# Gigabit_Ethernet.net
KiCad netlist of a schematic drawn in Altium Designer
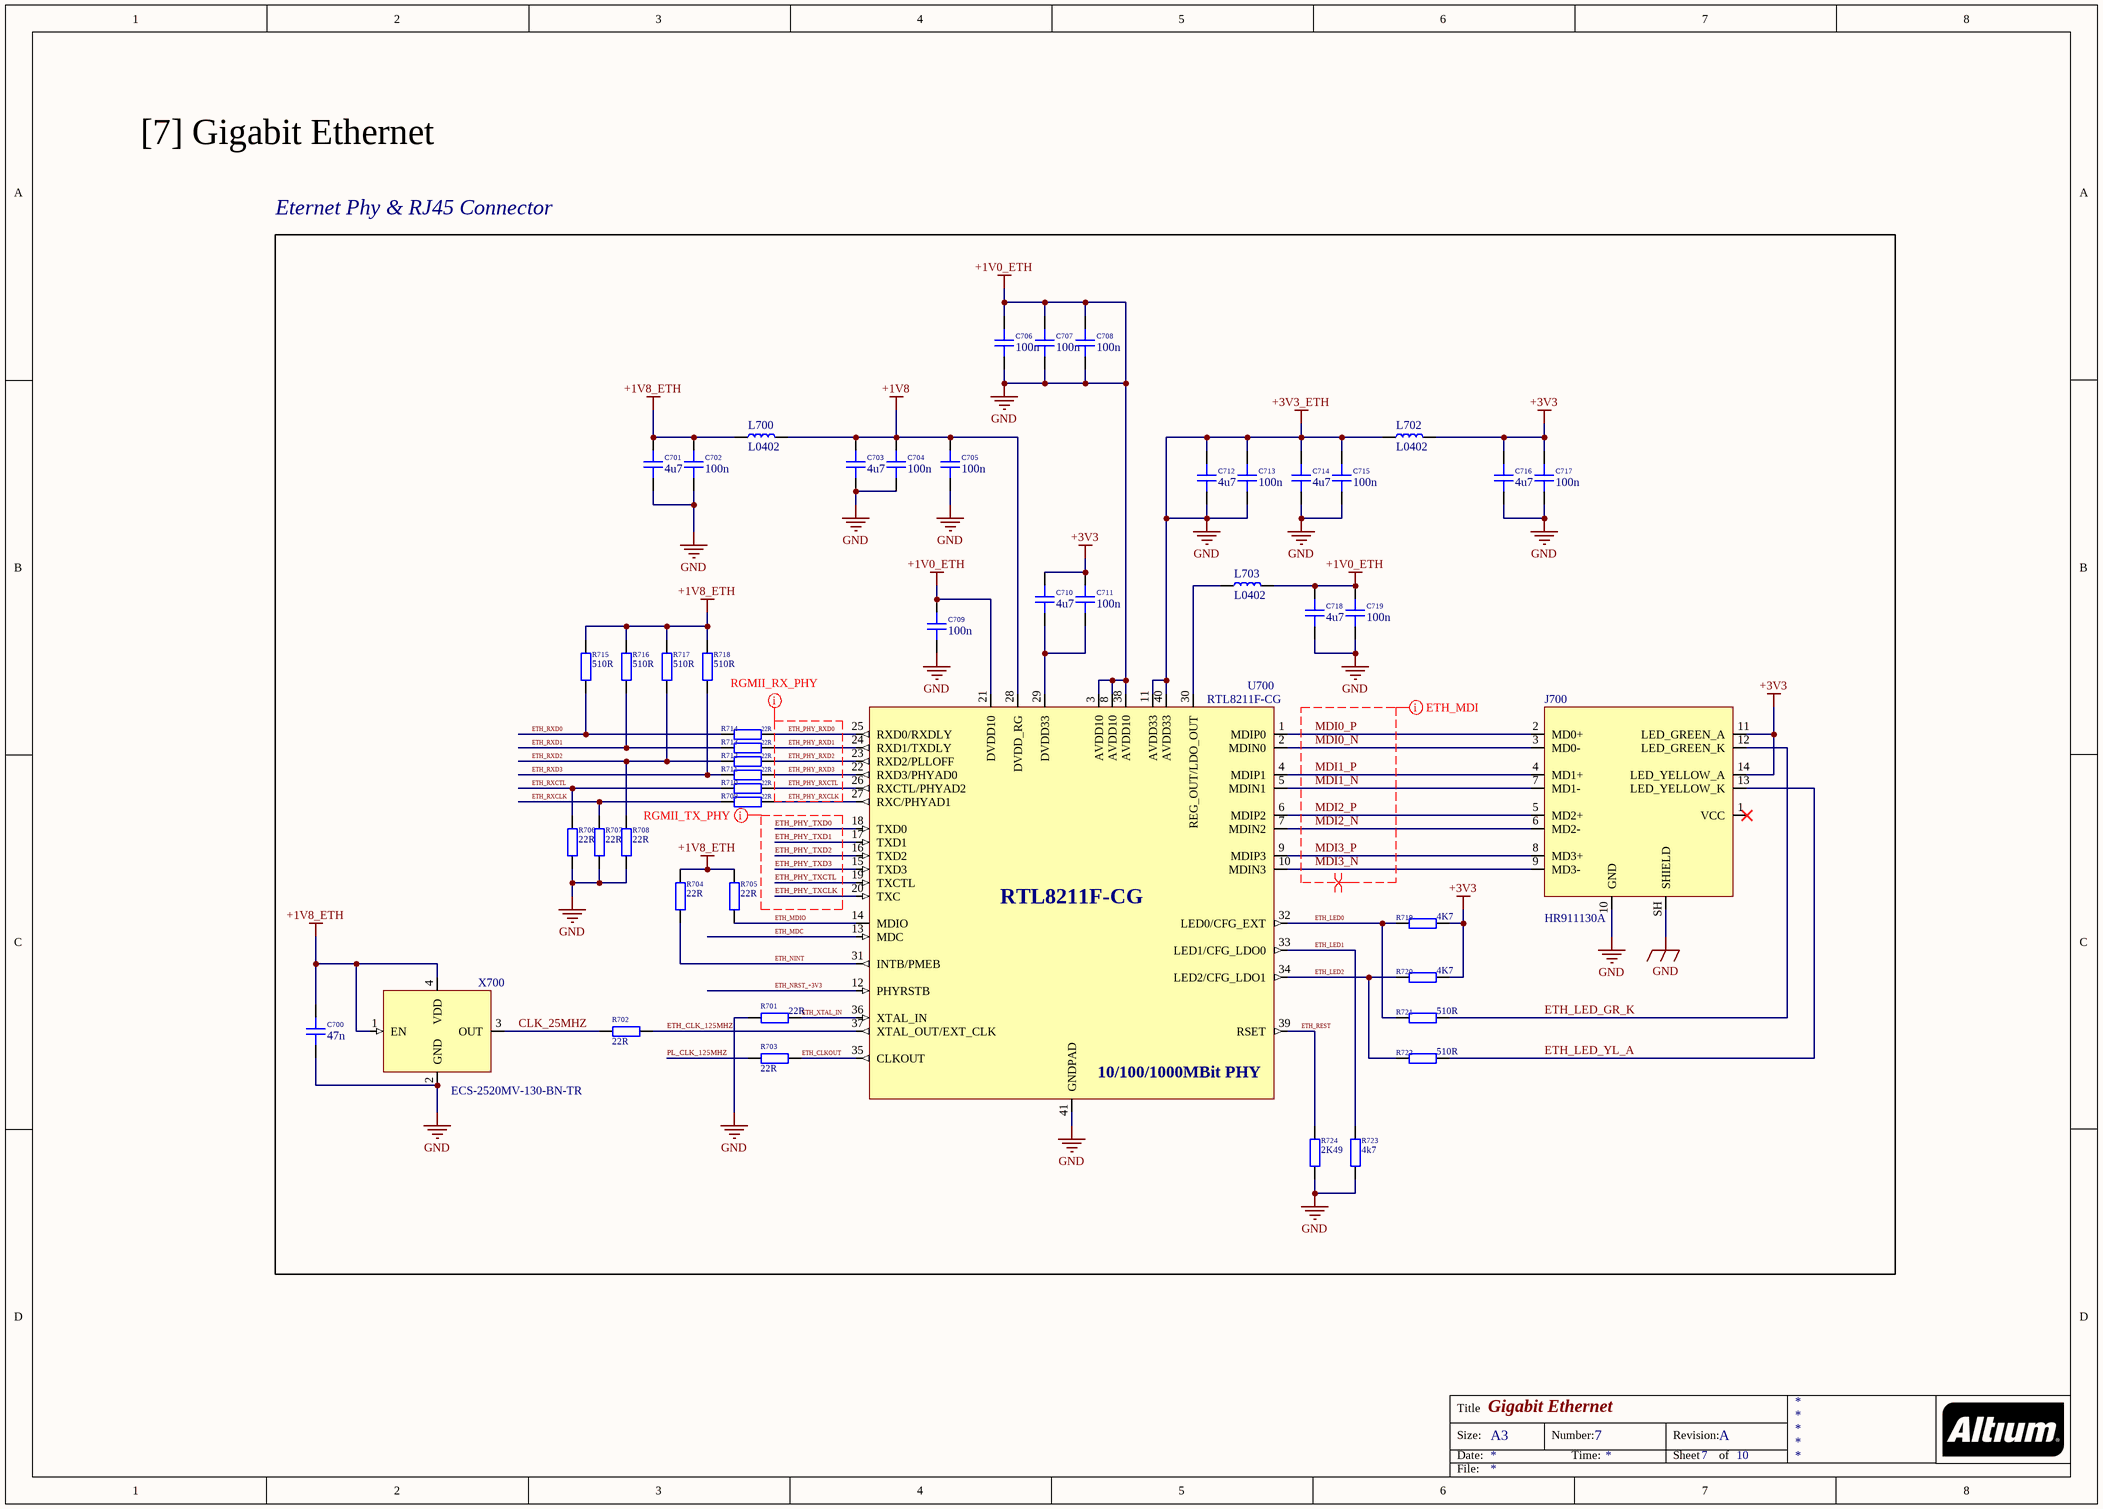
[diagram p0: Gigabit Ethernet.SchDoc]

(export (version "E")
  (design (tool "Eeschema 10.0.6"))
  (components
    (comp (ref "C700")
      (value "47n")
      (footprint "CAP_1210")
      (description "Capacitor SMD 1210")
      (libsource (lib "Schematic-Lib-PhilsLab") (part "CAP_1210"))
    )
    (comp (ref "C701")
      (value "4u7")
      (footprint "CAP_1210")
      (description "Capacitor SMD 1210")
      (libsource (lib "Schematic-Lib-PhilsLab") (part "CAP_1210"))
    )
    (comp (ref "C702")
      (value "100n")
      (footprint "CAP_1210")
      (description "Capacitor SMD 1210")
      (libsource (lib "Schematic-Lib-PhilsLab") (part "CAP_1210"))
    )
    (comp (ref "C703")
      (value "4u7")
      (footprint "CAP_1210")
      (description "Capacitor SMD 1210")
      (libsource (lib "Schematic-Lib-PhilsLab") (part "CAP_1210"))
    )
    (comp (ref "C704")
      (value "100n")
      (footprint "CAP_1210")
      (description "Capacitor SMD 1210")
      (libsource (lib "Schematic-Lib-PhilsLab") (part "CAP_1210"))
    )
    (comp (ref "C705")
      (value "100n")
      (footprint "CAP_1210")
      (description "Capacitor SMD 1210")
      (libsource (lib "Schematic-Lib-PhilsLab") (part "CAP_1210"))
    )
    (comp (ref "C706")
      (value "100n")
      (footprint "CAP_1210")
      (description "Capacitor SMD 1210")
      (libsource (lib "Schematic-Lib-PhilsLab") (part "CAP_1210"))
    )
    (comp (ref "C707")
      (value "100n")
      (footprint "CAP_1210")
      (description "Capacitor SMD 1210")
      (libsource (lib "Schematic-Lib-PhilsLab") (part "CAP_1210"))
    )
    (comp (ref "C708")
      (value "100n")
      (footprint "CAP_1210")
      (description "Capacitor SMD 1210")
      (libsource (lib "Schematic-Lib-PhilsLab") (part "CAP_1210"))
    )
    (comp (ref "C709")
      (value "100n")
      (footprint "CAP_1210")
      (description "Capacitor SMD 1210")
      (libsource (lib "Schematic-Lib-PhilsLab") (part "CAP_1210"))
    )
    (comp (ref "C710")
      (value "4u7")
      (footprint "CAP_1210")
      (description "Capacitor SMD 1210")
      (libsource (lib "Schematic-Lib-PhilsLab") (part "CAP_1210"))
    )
    (comp (ref "C711")
      (value "100n")
      (footprint "CAP_1210")
      (description "Capacitor SMD 1210")
      (libsource (lib "Schematic-Lib-PhilsLab") (part "CAP_1210"))
    )
    (comp (ref "C712")
      (value "4u7")
      (footprint "CAP_1210")
      (description "Capacitor SMD 1210")
      (libsource (lib "Schematic-Lib-PhilsLab") (part "CAP_1210"))
    )
    (comp (ref "C713")
      (value "100n")
      (footprint "CAP_1210")
      (description "Capacitor SMD 1210")
      (libsource (lib "Schematic-Lib-PhilsLab") (part "CAP_1210"))
    )
    (comp (ref "C714")
      (value "4u7")
      (footprint "CAP_1210")
      (description "Capacitor SMD 1210")
      (libsource (lib "Schematic-Lib-PhilsLab") (part "CAP_1210"))
    )
    (comp (ref "C715")
      (value "100n")
      (footprint "CAP_1210")
      (description "Capacitor SMD 1210")
      (libsource (lib "Schematic-Lib-PhilsLab") (part "CAP_1210"))
    )
    (comp (ref "C716")
      (value "4u7")
      (footprint "CAP_1210")
      (description "Capacitor SMD 1210")
      (libsource (lib "Schematic-Lib-PhilsLab") (part "CAP_1210"))
    )
    (comp (ref "C717")
      (value "100n")
      (footprint "CAP_1210")
      (description "Capacitor SMD 1210")
      (libsource (lib "Schematic-Lib-PhilsLab") (part "CAP_1210"))
    )
    (comp (ref "C718")
      (value "4u7")
      (footprint "CAP_1210")
      (description "Capacitor SMD 1210")
      (libsource (lib "Schematic-Lib-PhilsLab") (part "CAP_1210"))
    )
    (comp (ref "C719")
      (value "100n")
      (footprint "CAP_1210")
      (description "Capacitor SMD 1210")
      (libsource (lib "Schematic-Lib-PhilsLab") (part "CAP_1210"))
    )
    (comp (ref "J700")
      (value "HR911130A")
      (footprint "HR911130A")
      (description "100/1000Base-T Magnetics Single-Port RJ45 Connector with Integrated Magnetics and LEDs")
      (fields (field (name "MANUFACTURER") "Hanrun"))
      (libsource (lib "Schematic-Lib-PhilsLab") (part "HR911130A"))
    )
    (comp (ref "L700")
      (value "L0402")
      (footprint "IND_0402")
      (description "Inductor SMD 0402")
      (libsource (lib "Schematic-Lib-PhilsLab") (part "IND_0402"))
    )
    (comp (ref "L702")
      (value "L0402")
      (footprint "IND_0402")
      (description "Inductor SMD 0402")
      (libsource (lib "Schematic-Lib-PhilsLab") (part "IND_0402"))
    )
    (comp (ref "L703")
      (value "L0402")
      (footprint "IND_0402")
      (description "Inductor SMD 0402")
      (libsource (lib "Schematic-Lib-PhilsLab") (part "IND_0402"))
    )
    (comp (ref "R701")
      (value "22R")
      (footprint "RES_0402")
      (description "Resistor SMD 0402")
      (libsource (lib "Schematic-Lib-PhilsLab") (part "RES_0402"))
    )
    (comp (ref "R702")
      (value "22R")
      (footprint "RES_0402")
      (description "Resistor SMD 0402")
      (libsource (lib "Schematic-Lib-PhilsLab") (part "RES_0402"))
    )
    (comp (ref "R703")
      (value "22R")
      (footprint "RES_0402")
      (description "Resistor SMD 0402")
      (libsource (lib "Schematic-Lib-PhilsLab") (part "RES_0402"))
    )
    (comp (ref "R704")
      (value "22R")
      (footprint "RES_0402")
      (description "Resistor SMD 0402")
      (libsource (lib "Schematic-Lib-PhilsLab") (part "RES_0402"))
    )
    (comp (ref "R705")
      (value "22R")
      (footprint "RES_0402")
      (description "Resistor SMD 0402")
      (libsource (lib "Schematic-Lib-PhilsLab") (part "RES_0402"))
    )
    (comp (ref "R706")
      (value "22R")
      (footprint "RES_0402")
      (description "Resistor SMD 0402")
      (libsource (lib "Schematic-Lib-PhilsLab") (part "RES_0402"))
    )
    (comp (ref "R707")
      (value "22R")
      (footprint "RES_0402")
      (description "Resistor SMD 0402")
      (libsource (lib "Schematic-Lib-PhilsLab") (part "RES_0402"))
    )
    (comp (ref "R708")
      (value "22R")
      (footprint "RES_0402")
      (description "Resistor SMD 0402")
      (libsource (lib "Schematic-Lib-PhilsLab") (part "RES_0402"))
    )
    (comp (ref "R709")
      (value "22R")
      (footprint "RES_0402")
      (description "Resistor SMD 0402")
      (libsource (lib "Schematic-Lib-PhilsLab") (part "RES_0402"))
    )
    (comp (ref "R710")
      (value "22R")
      (footprint "RES_0402")
      (description "Resistor SMD 0402")
      (libsource (lib "Schematic-Lib-PhilsLab") (part "RES_0402"))
    )
    (comp (ref "R711")
      (value "22R")
      (footprint "RES_0402")
      (description "Resistor SMD 0402")
      (libsource (lib "Schematic-Lib-PhilsLab") (part "RES_0402"))
    )
    (comp (ref "R712")
      (value "22R")
      (footprint "RES_0402")
      (description "Resistor SMD 0402")
      (libsource (lib "Schematic-Lib-PhilsLab") (part "RES_0402"))
    )
    (comp (ref "R713")
      (value "22R")
      (footprint "RES_0402")
      (description "Resistor SMD 0402")
      (libsource (lib "Schematic-Lib-PhilsLab") (part "RES_0402"))
    )
    (comp (ref "R714")
      (value "22R")
      (footprint "RES_0402")
      (description "Resistor SMD 0402")
      (libsource (lib "Schematic-Lib-PhilsLab") (part "RES_0402"))
    )
    (comp (ref "R715")
      (value "510R")
      (footprint "RES_0402")
      (description "Resistor SMD 0402")
      (libsource (lib "Schematic-Lib-PhilsLab") (part "RES_0402"))
    )
    (comp (ref "R716")
      (value "510R")
      (footprint "RES_0402")
      (description "Resistor SMD 0402")
      (libsource (lib "Schematic-Lib-PhilsLab") (part "RES_0402"))
    )
    (comp (ref "R717")
      (value "510R")
      (footprint "RES_0402")
      (description "Resistor SMD 0402")
      (libsource (lib "Schematic-Lib-PhilsLab") (part "RES_0402"))
    )
    (comp (ref "R718")
      (value "510R")
      (footprint "RES_0402")
      (description "Resistor SMD 0402")
      (libsource (lib "Schematic-Lib-PhilsLab") (part "RES_0402"))
    )
    (comp (ref "R719")
      (value "4K7")
      (footprint "RES_0402")
      (description "Resistor SMD 0402")
      (libsource (lib "Schematic-Lib-PhilsLab") (part "RES_0402"))
    )
    (comp (ref "R720")
      (value "4K7")
      (footprint "RES_0402")
      (description "Resistor SMD 0402")
      (libsource (lib "Schematic-Lib-PhilsLab") (part "RES_0402"))
    )
    (comp (ref "R721")
      (value "510R")
      (footprint "RES_0402")
      (description "Resistor SMD 0402")
      (libsource (lib "Schematic-Lib-PhilsLab") (part "RES_0402"))
    )
    (comp (ref "R722")
      (value "510R")
      (footprint "RES_0402")
      (description "Resistor SMD 0402")
      (libsource (lib "Schematic-Lib-PhilsLab") (part "RES_0402"))
    )
    (comp (ref "R723")
      (value "4k7")
      (footprint "RES_0402")
      (description "Resistor SMD 0402")
      (libsource (lib "Schematic-Lib-PhilsLab") (part "RES_0402"))
    )
    (comp (ref "R724")
      (value "2K49")
      (footprint "RES_0402")
      (description "Resistor SMD 0402")
      (libsource (lib "Schematic-Lib-PhilsLab") (part "RES_0402"))
    )
    (comp (ref "U700")
      (value "RTL8211F-CG")
      (footprint "QFN-40-0.4-EP")
      (description "INTEGRATED 10/100/1000M ETHERNET PRECISION TRANSCEIVER")
      (fields (field (name "MANUFACTURER") "Realtek"))
      (libsource (lib "Schematic-Lib-PhilsLab") (part "RTL8211F-CG"))
    )
    (comp (ref "X700")
      (value "ECS-2520MV-130-BN-TR")
      (footprint "XTAL_2520")
      (fields (field (name "MANUFACTURER") "ECS"))
      (libsource (lib "Schematic-Lib-PhilsLab") (part "ECS-2520MV-130-BN-TR"))
    )
  )
  (nets
    (net (code "1") (name "+1V0_ETH") (class "Default")
      (node (ref "C700") (pin "1") (pinfunction "1_1") (pintype "passive"))
      (node (ref "C701") (pin "1") (pinfunction "1_1") (pintype "passive"))
      (node (ref "C702") (pin "1") (pinfunction "1_1") (pintype "passive"))
      (node (ref "C703") (pin "1") (pinfunction "1_1") (pintype "passive"))
      (node (ref "C704") (pin "1") (pinfunction "1_1") (pintype "passive"))
      (node (ref "C705") (pin "1") (pinfunction "1_1") (pintype "passive"))
      (node (ref "C706") (pin "1") (pinfunction "1_1") (pintype "passive"))
      (node (ref "C706") (pin "2") (pinfunction "2_2") (pintype "passive"))
      (node (ref "C707") (pin "1") (pinfunction "1_1") (pintype "passive"))
      (node (ref "C707") (pin "2") (pinfunction "2_2") (pintype "passive"))
      (node (ref "C708") (pin "1") (pinfunction "1_1") (pintype "passive"))
      (node (ref "C708") (pin "2") (pinfunction "2_2") (pintype "passive"))
      (node (ref "C709") (pin "1") (pinfunction "1_1") (pintype "passive"))
      (node (ref "C709") (pin "2") (pinfunction "2_2") (pintype "passive"))
      (node (ref "C712") (pin "1") (pinfunction "1_1") (pintype "passive"))
      (node (ref "C712") (pin "2") (pinfunction "2_2") (pintype "passive"))
      (node (ref "C713") (pin "1") (pinfunction "1_1") (pintype "passive"))
      (node (ref "C713") (pin "2") (pinfunction "2_2") (pintype "passive"))
      (node (ref "C714") (pin "1") (pinfunction "1_1") (pintype "passive"))
      (node (ref "C714") (pin "2") (pinfunction "2_2") (pintype "passive"))
      (node (ref "C715") (pin "1") (pinfunction "1_1") (pintype "passive"))
      (node (ref "C715") (pin "2") (pinfunction "2_2") (pintype "passive"))
      (node (ref "C716") (pin "1") (pinfunction "1_1") (pintype "passive"))
      (node (ref "C717") (pin "1") (pinfunction "1_1") (pintype "passive"))
      (node (ref "C718") (pin "1") (pinfunction "1_1") (pintype "passive"))
      (node (ref "C718") (pin "2") (pinfunction "2_2") (pintype "passive"))
      (node (ref "C719") (pin "1") (pinfunction "1_1") (pintype "passive"))
      (node (ref "C719") (pin "2") (pinfunction "2_2") (pintype "passive"))
      (node (ref "J700") (pin "10") (pinfunction "GND_10") (pintype "passive"))
      (node (ref "J700") (pin "SH") (pinfunction "SHIELD_SH") (pintype "passive"))
      (node (ref "L702") (pin "1") (pinfunction "1_1") (pintype "passive"))
      (node (ref "L703") (pin "2") (pinfunction "2_2") (pintype "passive"))
      (node (ref "R701") (pin "1") (pinfunction "1_1") (pintype "passive"))
      (node (ref "R706") (pin "1") (pinfunction "1_1") (pintype "passive"))
      (node (ref "R707") (pin "1") (pinfunction "1_1") (pintype "passive"))
      (node (ref "R708") (pin "1") (pinfunction "1_1") (pintype "passive"))
      (node (ref "R723") (pin "1") (pinfunction "1_1") (pintype "passive"))
      (node (ref "R724") (pin "1") (pinfunction "1_1") (pintype "passive"))
      (node (ref "U700") (pin "11") (pinfunction "AVDD33_11") (pintype "power_in"))
      (node (ref "U700") (pin "21") (pinfunction "DVDD10_21") (pintype "power_in"))
      (node (ref "U700") (pin "3") (pinfunction "AVDD10_3") (pintype "power_in"))
      (node (ref "U700") (pin "38") (pinfunction "AVDD10_38") (pintype "power_in"))
      (node (ref "U700") (pin "40") (pinfunction "AVDD33_40") (pintype "power_in"))
      (node (ref "U700") (pin "41") (pinfunction "GNDPAD_41") (pintype "power_in"))
      (node (ref "U700") (pin "8") (pinfunction "AVDD10_8") (pintype "power_in"))
      (node (ref "X700") (pin "2") (pinfunction "GND_2") (pintype "power_in"))
    )
    (net (code "2") (name "+1V8") (class "Default")
      (node (ref "C703") (pin "2") (pinfunction "2_2") (pintype "passive"))
      (node (ref "C704") (pin "2") (pinfunction "2_2") (pintype "passive"))
      (node (ref "C705") (pin "2") (pinfunction "2_2") (pintype "passive"))
      (node (ref "L700") (pin "2") (pinfunction "2_2") (pintype "passive"))
      (node (ref "U700") (pin "28") (pinfunction "DVDD_RG_28") (pintype "power_in"))
    )
    (net (code "3") (name "+1V8_ETH") (class "Default")
      (node (ref "C700") (pin "2") (pinfunction "2_2") (pintype "passive"))
      (node (ref "C701") (pin "2") (pinfunction "2_2") (pintype "passive"))
      (node (ref "C702") (pin "2") (pinfunction "2_2") (pintype "passive"))
      (node (ref "L700") (pin "1") (pinfunction "1_1") (pintype "passive"))
      (node (ref "R704") (pin "2") (pinfunction "2_2") (pintype "passive"))
      (node (ref "R705") (pin "2") (pinfunction "2_2") (pintype "passive"))
      (node (ref "R715") (pin "2") (pinfunction "2_2") (pintype "passive"))
      (node (ref "R716") (pin "2") (pinfunction "2_2") (pintype "passive"))
      (node (ref "R717") (pin "2") (pinfunction "2_2") (pintype "passive"))
      (node (ref "R718") (pin "2") (pinfunction "2_2") (pintype "passive"))
      (node (ref "X700") (pin "1") (pinfunction "EN_1") (pintype "input"))
      (node (ref "X700") (pin "4") (pinfunction "VDD_4") (pintype "power_in"))
    )
    (net (code "4") (name "+3V3") (class "Default")
      (node (ref "C710") (pin "2") (pinfunction "2_2") (pintype "passive"))
      (node (ref "C711") (pin "2") (pinfunction "2_2") (pintype "passive"))
      (node (ref "C716") (pin "2") (pinfunction "2_2") (pintype "passive"))
      (node (ref "C717") (pin "2") (pinfunction "2_2") (pintype "passive"))
      (node (ref "J700") (pin "11") (pinfunction "LED_GREEN_A_11") (pintype "passive"))
      (node (ref "J700") (pin "14") (pinfunction "LED_YELLOW_A_14") (pintype "passive"))
      (node (ref "L702") (pin "2") (pinfunction "2_2") (pintype "passive"))
      (node (ref "R719") (pin "2") (pinfunction "2_2") (pintype "passive"))
      (node (ref "R720") (pin "2") (pinfunction "2_2") (pintype "passive"))
    )
    (net (code "5") (name "/CLK_25MHZ") (class "Default")
      (node (ref "R702") (pin "2") (pinfunction "2_2") (pintype "passive"))
      (node (ref "X700") (pin "3") (pinfunction "OUT_3") (pintype "passive"))
    )
    (net (code "6") (name "/ETH_CLKOUT") (class "Default")
      (node (ref "R703") (pin "1") (pinfunction "1_1") (pintype "passive"))
      (node (ref "U700") (pin "35") (pinfunction "CLKOUT_35") (pintype "output"))
    )
    (net (code "7") (name "/ETH_CLK_125MHZ") (class "Default")
      (node (ref "R702") (pin "1") (pinfunction "1_1") (pintype "passive"))
      (node (ref "U700") (pin "37") (pinfunction "XTAL_OUT/EXT_CLK_37") (pintype "output"))
    )
    (net (code "8") (name "/ETH_LED0") (class "Default")
      (node (ref "R719") (pin "1") (pinfunction "1_1") (pintype "passive"))
      (node (ref "R721") (pin "1") (pinfunction "1_1") (pintype "passive"))
      (node (ref "U700") (pin "32") (pinfunction "LED0/CFG_EXT_32") (pintype "output"))
    )
    (net (code "9") (name "/ETH_LED1") (class "Default")
      (node (ref "R723") (pin "2") (pinfunction "2_2") (pintype "passive"))
      (node (ref "U700") (pin "33") (pinfunction "LED1/CFG_LDO0_33") (pintype "output"))
    )
    (net (code "10") (name "/ETH_LED2") (class "Default")
      (node (ref "R720") (pin "1") (pinfunction "1_1") (pintype "passive"))
      (node (ref "R722") (pin "1") (pinfunction "1_1") (pintype "passive"))
      (node (ref "U700") (pin "34") (pinfunction "LED2/CFG_LDO1_34") (pintype "output"))
    )
    (net (code "11") (name "/ETH_LED_GR_K") (class "Default")
      (node (ref "J700") (pin "12") (pinfunction "LED_GREEN_K_12") (pintype "passive"))
      (node (ref "R721") (pin "2") (pinfunction "2_2") (pintype "passive"))
    )
    (net (code "12") (name "/ETH_LED_YL_A") (class "Default")
      (node (ref "J700") (pin "13") (pinfunction "LED_YELLOW_K_13") (pintype "passive"))
      (node (ref "R722") (pin "2") (pinfunction "2_2") (pintype "passive"))
    )
    (net (code "13") (name "/ETH_MDC") (class "Default")
      (node (ref "U700") (pin "13") (pinfunction "MDC_13") (pintype "input"))
    )
    (net (code "14") (name "/ETH_MDIO") (class "Default")
      (node (ref "R705") (pin "1") (pinfunction "1_1") (pintype "passive"))
      (node (ref "U700") (pin "14") (pinfunction "MDIO_14") (pintype "bidirectional"))
    )
    (net (code "15") (name "/ETH_NINT") (class "Default")
      (node (ref "R704") (pin "1") (pinfunction "1_1") (pintype "passive"))
      (node (ref "U700") (pin "31") (pinfunction "INTB/PMEB_31") (pintype "output"))
    )
    (net (code "16") (name "/ETH_NRST_+3V3") (class "Default")
      (node (ref "U700") (pin "12") (pinfunction "PHYRSTB_12") (pintype "input"))
    )
    (net (code "17") (name "/ETH_PHY_RXCLK") (class "Default")
      (node (ref "R709") (pin "2") (pinfunction "2_2") (pintype "passive"))
      (node (ref "U700") (pin "27") (pinfunction "RXC/PHYAD1_27") (pintype "output"))
    )
    (net (code "18") (name "/ETH_PHY_RXCTL") (class "Default")
      (node (ref "R710") (pin "2") (pinfunction "2_2") (pintype "passive"))
      (node (ref "U700") (pin "26") (pinfunction "RXCTL/PHYAD2_26") (pintype "output"))
    )
    (net (code "19") (name "/ETH_PHY_RXD0") (class "Default")
      (node (ref "R714") (pin "2") (pinfunction "2_2") (pintype "passive"))
      (node (ref "U700") (pin "25") (pinfunction "RXD0/RXDLY_25") (pintype "output"))
    )
    (net (code "20") (name "/ETH_PHY_RXD1") (class "Default")
      (node (ref "R713") (pin "2") (pinfunction "2_2") (pintype "passive"))
      (node (ref "U700") (pin "24") (pinfunction "RXD1/TXDLY_24") (pintype "output"))
    )
    (net (code "21") (name "/ETH_PHY_RXD2") (class "Default")
      (node (ref "R712") (pin "2") (pinfunction "2_2") (pintype "passive"))
      (node (ref "U700") (pin "23") (pinfunction "RXD2/PLLOFF_23") (pintype "output"))
    )
    (net (code "22") (name "/ETH_PHY_RXD3") (class "Default")
      (node (ref "R711") (pin "2") (pinfunction "2_2") (pintype "passive"))
      (node (ref "U700") (pin "22") (pinfunction "RXD3/PHYAD0_22") (pintype "output"))
    )
    (net (code "23") (name "/ETH_PHY_TXCLK") (class "Default")
      (node (ref "U700") (pin "20") (pinfunction "TXC_20") (pintype "input"))
    )
    (net (code "24") (name "/ETH_PHY_TXCTL") (class "Default")
      (node (ref "U700") (pin "19") (pinfunction "TXCTL_19") (pintype "input"))
    )
    (net (code "25") (name "/ETH_PHY_TXD0") (class "Default")
      (node (ref "U700") (pin "18") (pinfunction "TXD0_18") (pintype "input"))
    )
    (net (code "26") (name "/ETH_PHY_TXD1") (class "Default")
      (node (ref "U700") (pin "17") (pinfunction "TXD1_17") (pintype "input"))
    )
    (net (code "27") (name "/ETH_PHY_TXD2") (class "Default")
      (node (ref "U700") (pin "16") (pinfunction "TXD2_16") (pintype "input"))
    )
    (net (code "28") (name "/ETH_PHY_TXD3") (class "Default")
      (node (ref "U700") (pin "15") (pinfunction "TXD3_15") (pintype "input"))
    )
    (net (code "29") (name "/ETH_REST") (class "Default")
      (node (ref "R724") (pin "2") (pinfunction "2_2") (pintype "passive"))
      (node (ref "U700") (pin "39") (pinfunction "RSET_39") (pintype "output"))
    )
    (net (code "30") (name "/ETH_RXCLK") (class "Default")
      (node (ref "R707") (pin "2") (pinfunction "2_2") (pintype "passive"))
      (node (ref "R709") (pin "1") (pinfunction "1_1") (pintype "passive"))
    )
    (net (code "31") (name "/ETH_RXCTL") (class "Default")
      (node (ref "R706") (pin "2") (pinfunction "2_2") (pintype "passive"))
      (node (ref "R710") (pin "1") (pinfunction "1_1") (pintype "passive"))
    )
    (net (code "32") (name "/ETH_RXD0") (class "Default")
      (node (ref "R714") (pin "1") (pinfunction "1_1") (pintype "passive"))
      (node (ref "R715") (pin "1") (pinfunction "1_1") (pintype "passive"))
    )
    (net (code "33") (name "/ETH_RXD1") (class "Default")
      (node (ref "R713") (pin "1") (pinfunction "1_1") (pintype "passive"))
      (node (ref "R716") (pin "1") (pinfunction "1_1") (pintype "passive"))
    )
    (net (code "34") (name "/ETH_RXD2") (class "Default")
      (node (ref "R708") (pin "2") (pinfunction "2_2") (pintype "passive"))
      (node (ref "R712") (pin "1") (pinfunction "1_1") (pintype "passive"))
      (node (ref "R717") (pin "1") (pinfunction "1_1") (pintype "passive"))
    )
    (net (code "35") (name "/ETH_RXD3") (class "Default")
      (node (ref "R711") (pin "1") (pinfunction "1_1") (pintype "passive"))
      (node (ref "R718") (pin "1") (pinfunction "1_1") (pintype "passive"))
    )
    (net (code "36") (name "/ETH_XTAL_IN") (class "Default")
      (node (ref "R701") (pin "2") (pinfunction "2_2") (pintype "passive"))
      (node (ref "U700") (pin "36") (pinfunction "XTAL_IN_36") (pintype "input"))
    )
    (net (code "37") (name "/MDI0_N") (class "Default")
      (node (ref "J700") (pin "3") (pinfunction "MD0-_3") (pintype "passive"))
      (node (ref "U700") (pin "2") (pinfunction "MDIN0_2") (pintype "bidirectional"))
    )
    (net (code "38") (name "/MDI0_P") (class "Default")
      (node (ref "J700") (pin "2") (pinfunction "MD0+_2") (pintype "passive"))
      (node (ref "U700") (pin "1") (pinfunction "MDIP0_1") (pintype "bidirectional"))
    )
    (net (code "39") (name "/MDI1_N") (class "Default")
      (node (ref "J700") (pin "7") (pinfunction "MD1-_7") (pintype "passive"))
      (node (ref "U700") (pin "5") (pinfunction "MDIN1_5") (pintype "bidirectional"))
    )
    (net (code "40") (name "/MDI1_P") (class "Default")
      (node (ref "J700") (pin "4") (pinfunction "MD1+_4") (pintype "passive"))
      (node (ref "U700") (pin "4") (pinfunction "MDIP1_4") (pintype "bidirectional"))
    )
    (net (code "41") (name "/MDI2_N") (class "Default")
      (node (ref "J700") (pin "6") (pinfunction "MD2-_6") (pintype "passive"))
      (node (ref "U700") (pin "7") (pinfunction "MDIN2_7") (pintype "bidirectional"))
    )
    (net (code "42") (name "/MDI2_P") (class "Default")
      (node (ref "J700") (pin "5") (pinfunction "MD2+_5") (pintype "passive"))
      (node (ref "U700") (pin "6") (pinfunction "MDIP2_6") (pintype "bidirectional"))
    )
    (net (code "43") (name "/MDI3_N") (class "Default")
      (node (ref "J700") (pin "9") (pinfunction "MD3-_9") (pintype "passive"))
      (node (ref "U700") (pin "10") (pinfunction "MDIN3_10") (pintype "bidirectional"))
    )
    (net (code "44") (name "/MDI3_P") (class "Default")
      (node (ref "J700") (pin "8") (pinfunction "MD3+_8") (pintype "passive"))
      (node (ref "U700") (pin "9") (pinfunction "MDIP3_9") (pintype "bidirectional"))
    )
    (net (code "45") (name "/PL_CLK_125MHZ") (class "Default")
      (node (ref "R703") (pin "2") (pinfunction "2_2") (pintype "passive"))
    )
    (net (code "46") (name "Net-(U700-DVDD33)") (class "Default")
      (node (ref "C710") (pin "1") (pinfunction "1_1") (pintype "passive"))
      (node (ref "C711") (pin "1") (pinfunction "1_1") (pintype "passive"))
      (node (ref "U700") (pin "29") (pinfunction "DVDD33_29") (pintype "power_in"))
    )
    (net (code "47") (name "Net-(U700-REG_OUT{slash}LDO_OUT)") (class "Default")
      (node (ref "L703") (pin "1") (pinfunction "1_1") (pintype "passive"))
      (node (ref "U700") (pin "30") (pinfunction "REG_OUT/LDO_OUT_30") (pintype "power_in"))
    )
    (net (code "48") (name "unconnected-(J700-VCC-Pad1)") (class "Default")
      (node (ref "J700") (pin "1") (pinfunction "VCC_1") (pintype "passive+no_connect"))
    )
  )
)
